# interface.net
KiCad netlist of a schematic drawn in EAGLE
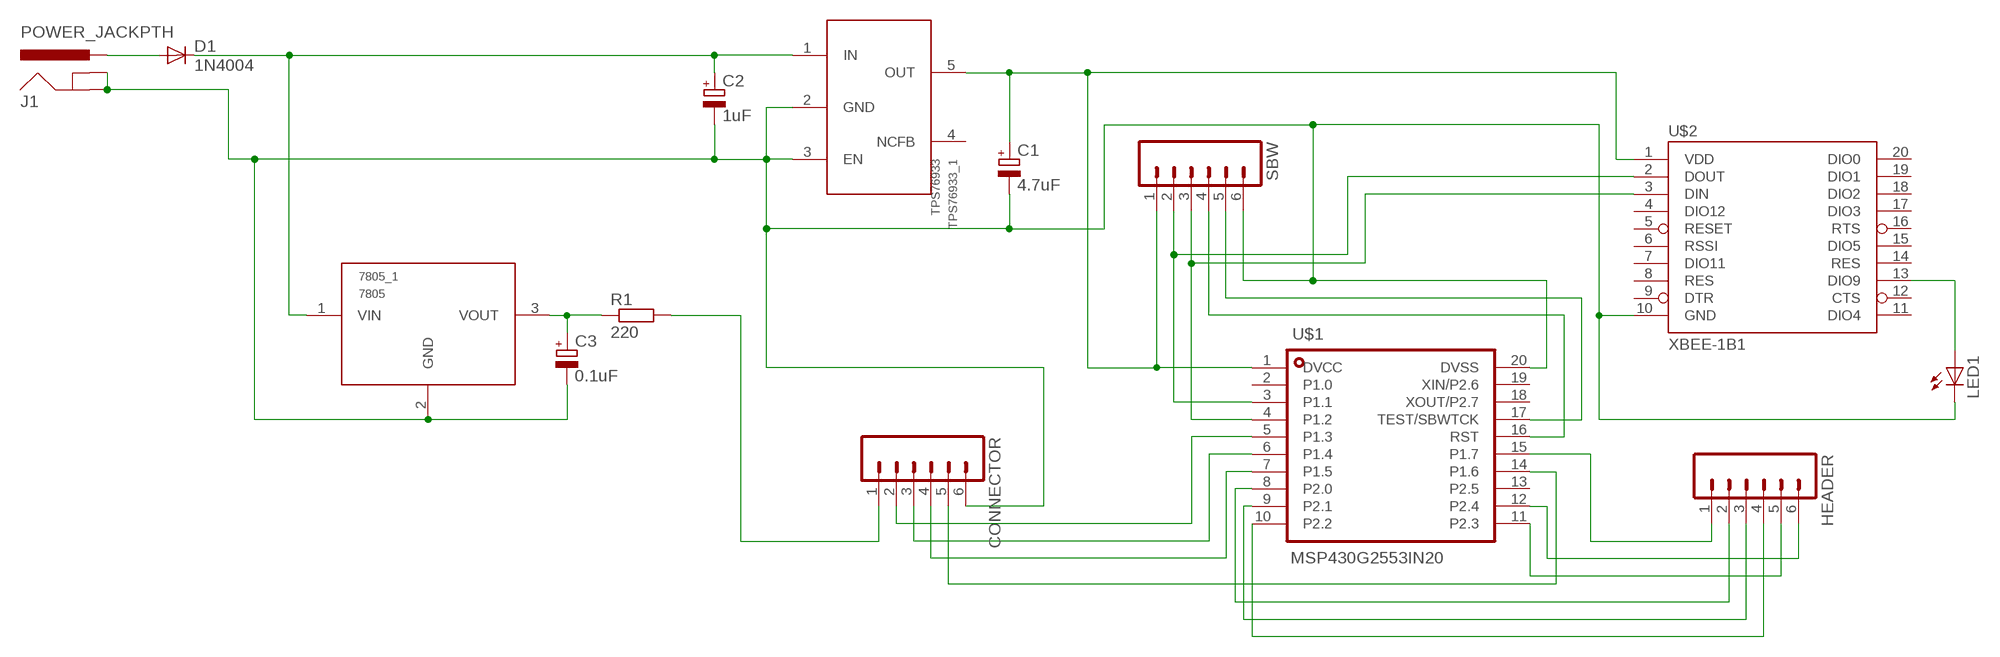
[diagram p0: schematic, sheet 1]

(export (version "E")
  (design (tool "Eeschema 10.0.6"))
  (components
    (comp (ref "7805_1")
      (value "7805")
      (footprint "eagle-import:TO-220")
      (libsource (lib "eagle-import") (part "7805"))
    )
    (comp (ref "C1")
      (value "4.7uF")
      (footprint "eagle-import:E1,8-4")
      (libsource (lib "eagle-import") (part "CPOL-EUE1.8-4"))
    )
    (comp (ref "C2")
      (value "1uF")
      (footprint "eagle-import:E1,8-4")
      (libsource (lib "eagle-import") (part "CPOL-EUE1.8-4"))
    )
    (comp (ref "C3")
      (value "0.1uF")
      (footprint "eagle-import:E1,8-4")
      (libsource (lib "eagle-import") (part "CPOL-EUE1.8-4"))
    )
    (comp (ref "CONNECTOR")
      (value "M06_90SIP")
      (footprint "eagle-import:1X06_90")
      (libsource (lib "eagle-import") (part "M06_90SIP"))
    )
    (comp (ref "D1")
      (value "1N4004")
      (footprint "eagle-import:DO41-10")
      (libsource (lib "eagle-import") (part "1N4004"))
    )
    (comp (ref "HEADER")
      (value "M06_180SIP")
      (footprint "eagle-import:1X06_180")
      (libsource (lib "eagle-import") (part "M06_180SIP"))
    )
    (comp (ref "J1")
      (value "POWER_JACKPTH")
      (footprint "eagle-import:POWER_JACK_PTH")
      (libsource (lib "eagle-import") (part "POWER_JACKPTH"))
    )
    (comp (ref "LED1")
      (value "LED3MM")
      (footprint "eagle-import:LED3MM")
      (libsource (lib "eagle-import") (part "LED3MM"))
    )
    (comp (ref "R1")
      (value "220")
      (footprint "eagle-import:0204_7")
      (libsource (lib "eagle-import") (part "R-EU_0204/7"))
    )
    (comp (ref "SBW")
      (value "M06_180SIP")
      (footprint "eagle-import:1X06_180")
      (libsource (lib "eagle-import") (part "M06_180SIP"))
    )
    (comp (ref "TPS76933_1")
      (value "TPS76933")
      (footprint "eagle-import:SOT23-5")
      (libsource (lib "eagle-import") (part "TPS76933"))
    )
    (comp (ref "U$1")
      (value "MSP430G2553IN20")
      (footprint "eagle-import:DIP20")
      (libsource (lib "eagle-import") (part "MSP430G2553IN20"))
    )
    (comp (ref "U$2")
      (value "XBEE-1B1")
      (footprint "eagle-import:XBEE-1")
      (libsource (lib "eagle-import") (part "XBEE-1B1"))
    )
  )
  (nets
    (net (code "1") (name "Net-(7805_1-GND)") (class "Default")
      (node (ref "7805_1") (pin "2") (pinfunction "GND_2") (pintype "bidirectional"))
      (node (ref "C1") (pin "-") (pinfunction "-_-") (pintype "passive"))
      (node (ref "C2") (pin "-") (pinfunction "-_-") (pintype "passive"))
      (node (ref "C3") (pin "-") (pinfunction "-_-") (pintype "passive"))
      (node (ref "CONNECTOR") (pin "6") (pinfunction "6_6") (pintype "passive"))
      (node (ref "J1") (pin "GND") (pinfunction "GND_GND") (pintype "bidirectional"))
      (node (ref "J1") (pin "GNDBREAK") (pinfunction "GNDBREAK_GNDBREAK") (pintype "bidirectional"))
      (node (ref "LED1") (pin "K") (pinfunction "C_K") (pintype "passive"))
      (node (ref "SBW") (pin "6") (pinfunction "6_6") (pintype "passive"))
      (node (ref "TPS76933_1") (pin "2") (pinfunction "GND_2") (pintype "bidirectional"))
      (node (ref "TPS76933_1") (pin "3") (pinfunction "EN_3") (pintype "bidirectional"))
      (node (ref "U$1") (pin "20") (pinfunction "DVSS_20") (pintype "power_in"))
      (node (ref "U$2") (pin "10") (pinfunction "GND_10") (pintype "power_in"))
    )
    (net (code "2") (name "Net-(7805_1-VIN)") (class "Default")
      (node (ref "7805_1") (pin "1") (pinfunction "VIN_1") (pintype "bidirectional"))
      (node (ref "C2") (pin "+") (pinfunction "+_+") (pintype "passive"))
      (node (ref "D1") (pin "C") (pinfunction "C_C") (pintype "passive"))
      (node (ref "TPS76933_1") (pin "1") (pinfunction "IN_1") (pintype "bidirectional"))
    )
    (net (code "3") (name "Net-(7805_1-VOUT)") (class "Default")
      (node (ref "7805_1") (pin "3") (pinfunction "VOUT_3") (pintype "bidirectional"))
      (node (ref "C3") (pin "+") (pinfunction "+_+") (pintype "passive"))
      (node (ref "R1") (pin "1") (pinfunction "1_1") (pintype "passive"))
    )
    (net (code "4") (name "Net-(CONNECTOR-Pad1)") (class "Default")
      (node (ref "CONNECTOR") (pin "1") (pinfunction "1_1") (pintype "passive"))
      (node (ref "R1") (pin "2") (pinfunction "2_2") (pintype "passive"))
    )
    (net (code "5") (name "Net-(D1-PadA)") (class "Default")
      (node (ref "D1") (pin "A") (pinfunction "A_A") (pintype "passive"))
      (node (ref "J1") (pin "PWR") (pinfunction "PWR_PWR") (pintype "bidirectional"))
    )
    (net (code "6") (name "Net-(TPS76933_1-OUT)") (class "Default")
      (node (ref "C1") (pin "+") (pinfunction "+_+") (pintype "passive"))
      (node (ref "SBW") (pin "1") (pinfunction "1_1") (pintype "passive"))
      (node (ref "TPS76933_1") (pin "5") (pinfunction "OUT_5") (pintype "bidirectional"))
      (node (ref "U$1") (pin "1") (pinfunction "DVCC_1") (pintype "power_in"))
      (node (ref "U$2") (pin "1") (pinfunction "VDD_1") (pintype "power_in"))
    )
    (net (code "7") (name "Net-(U$1-P1.1)") (class "Default")
      (node (ref "SBW") (pin "2") (pinfunction "2_2") (pintype "passive"))
      (node (ref "U$1") (pin "3") (pinfunction "P1.1_3") (pintype "bidirectional"))
      (node (ref "U$2") (pin "2") (pinfunction "DOUT_2") (pintype "output"))
    )
    (net (code "8") (name "Net-(U$1-P1.2)") (class "Default")
      (node (ref "SBW") (pin "3") (pinfunction "3_3") (pintype "passive"))
      (node (ref "U$1") (pin "4") (pinfunction "P1.2_4") (pintype "bidirectional"))
      (node (ref "U$2") (pin "3") (pinfunction "DIN_3") (pintype "input"))
    )
    (net (code "9") (name "Net-(U$1-P1.3)") (class "Default")
      (node (ref "CONNECTOR") (pin "2") (pinfunction "2_2") (pintype "passive"))
      (node (ref "U$1") (pin "5") (pinfunction "P1.3_5") (pintype "bidirectional"))
    )
    (net (code "10") (name "Net-(U$1-P1.4)") (class "Default")
      (node (ref "CONNECTOR") (pin "3") (pinfunction "3_3") (pintype "passive"))
      (node (ref "U$1") (pin "6") (pinfunction "P1.4_6") (pintype "bidirectional"))
    )
    (net (code "11") (name "Net-(U$1-P1.5)") (class "Default")
      (node (ref "CONNECTOR") (pin "4") (pinfunction "4_4") (pintype "passive"))
      (node (ref "U$1") (pin "7") (pinfunction "P1.5_7") (pintype "bidirectional"))
    )
    (net (code "12") (name "Net-(U$1-P1.6)") (class "Default")
      (node (ref "CONNECTOR") (pin "5") (pinfunction "5_5") (pintype "passive"))
      (node (ref "U$1") (pin "14") (pinfunction "P1.6_14") (pintype "bidirectional"))
    )
    (net (code "13") (name "Net-(U$1-P1.7)") (class "Default")
      (node (ref "HEADER") (pin "1") (pinfunction "1_1") (pintype "passive"))
      (node (ref "U$1") (pin "15") (pinfunction "P1.7_15") (pintype "bidirectional"))
    )
    (net (code "14") (name "Net-(U$1-P2.0)") (class "Default")
      (node (ref "HEADER") (pin "2") (pinfunction "2_2") (pintype "passive"))
      (node (ref "U$1") (pin "8") (pinfunction "P2.0_8") (pintype "bidirectional"))
    )
    (net (code "15") (name "Net-(U$1-P2.1)") (class "Default")
      (node (ref "HEADER") (pin "3") (pinfunction "3_3") (pintype "passive"))
      (node (ref "U$1") (pin "9") (pinfunction "P2.1_9") (pintype "bidirectional"))
    )
    (net (code "16") (name "Net-(U$1-P2.2)") (class "Default")
      (node (ref "HEADER") (pin "4") (pinfunction "4_4") (pintype "passive"))
      (node (ref "U$1") (pin "10") (pinfunction "P2.2_10") (pintype "bidirectional"))
    )
    (net (code "17") (name "Net-(U$1-P2.3)") (class "Default")
      (node (ref "HEADER") (pin "5") (pinfunction "5_5") (pintype "passive"))
      (node (ref "U$1") (pin "11") (pinfunction "P2.3_11") (pintype "bidirectional"))
    )
    (net (code "18") (name "Net-(U$1-P2.4)") (class "Default")
      (node (ref "HEADER") (pin "6") (pinfunction "6_6") (pintype "passive"))
      (node (ref "U$1") (pin "12") (pinfunction "P2.4_12") (pintype "bidirectional"))
    )
    (net (code "19") (name "Net-(U$1-RST)") (class "Default")
      (node (ref "SBW") (pin "4") (pinfunction "4_4") (pintype "passive"))
      (node (ref "U$1") (pin "16") (pinfunction "RST_16") (pintype "bidirectional"))
    )
    (net (code "20") (name "Net-(U$1-TEST{slash}SBWTCK)") (class "Default")
      (node (ref "SBW") (pin "5") (pinfunction "5_5") (pintype "passive"))
      (node (ref "U$1") (pin "17") (pinfunction "TEST/SBWTCK_17") (pintype "bidirectional"))
    )
    (net (code "21") (name "Net-(U$2-DIO9)") (class "Default")
      (node (ref "LED1") (pin "A") (pinfunction "A_A") (pintype "passive"))
      (node (ref "U$2") (pin "13") (pinfunction "DIO9_13") (pintype "bidirectional"))
    )
    (net (code "22") (name "unconnected-(TPS76933_1-NCFB-Pad4)") (class "Default")
      (node (ref "TPS76933_1") (pin "4") (pinfunction "NCFB_4") (pintype "bidirectional"))
    )
    (net (code "23") (name "unconnected-(U$1-P1.0-Pad2)") (class "Default")
      (node (ref "U$1") (pin "2") (pinfunction "P1.0_2") (pintype "bidirectional"))
    )
    (net (code "24") (name "unconnected-(U$1-P2.5-Pad13)") (class "Default")
      (node (ref "U$1") (pin "13") (pinfunction "P2.5_13") (pintype "bidirectional"))
    )
    (net (code "25") (name "unconnected-(U$1-XIN{slash}P2.6-Pad19)") (class "Default")
      (node (ref "U$1") (pin "19") (pinfunction "XIN/P2.6_19") (pintype "bidirectional"))
    )
    (net (code "26") (name "unconnected-(U$1-XOUT{slash}P2.7-Pad18)") (class "Default")
      (node (ref "U$1") (pin "18") (pinfunction "XOUT/P2.7_18") (pintype "bidirectional"))
    )
    (net (code "27") (name "unconnected-(U$2-CTS-Pad12)") (class "Default")
      (node (ref "U$2") (pin "12") (pinfunction "CTS_12") (pintype "output"))
    )
    (net (code "28") (name "unconnected-(U$2-DIO0-Pad20)") (class "Default")
      (node (ref "U$2") (pin "20") (pinfunction "DIO0_20") (pintype "bidirectional"))
    )
    (net (code "29") (name "unconnected-(U$2-DIO1-Pad19)") (class "Default")
      (node (ref "U$2") (pin "19") (pinfunction "DIO1_19") (pintype "bidirectional"))
    )
    (net (code "30") (name "unconnected-(U$2-DIO2-Pad18)") (class "Default")
      (node (ref "U$2") (pin "18") (pinfunction "DIO2_18") (pintype "bidirectional"))
    )
    (net (code "31") (name "unconnected-(U$2-DIO3-Pad17)") (class "Default")
      (node (ref "U$2") (pin "17") (pinfunction "DIO3_17") (pintype "bidirectional"))
    )
    (net (code "32") (name "unconnected-(U$2-DIO4-Pad11)") (class "Default")
      (node (ref "U$2") (pin "11") (pinfunction "DIO4_11") (pintype "bidirectional"))
    )
    (net (code "33") (name "unconnected-(U$2-DIO5-Pad15)") (class "Default")
      (node (ref "U$2") (pin "15") (pinfunction "DIO5_15") (pintype "bidirectional"))
    )
    (net (code "34") (name "unconnected-(U$2-DIO11-Pad7)") (class "Default")
      (node (ref "U$2") (pin "7") (pinfunction "DIO11_7") (pintype "bidirectional"))
    )
    (net (code "35") (name "unconnected-(U$2-DIO12-Pad4)") (class "Default")
      (node (ref "U$2") (pin "4") (pinfunction "DIO12_4") (pintype "bidirectional"))
    )
    (net (code "36") (name "unconnected-(U$2-DTR-Pad9)") (class "Default")
      (node (ref "U$2") (pin "9") (pinfunction "DTR_9") (pintype "bidirectional"))
    )
    (net (code "37") (name "unconnected-(U$2-RES-Pad8)") (class "Default")
      (node (ref "U$2") (pin "8") (pinfunction "RES_8") (pintype "bidirectional"))
    )
    (net (code "38") (name "unconnected-(U$2-RES-Pad14)") (class "Default")
      (node (ref "U$2") (pin "14") (pinfunction "RES_14") (pintype "bidirectional"))
    )
    (net (code "39") (name "unconnected-(U$2-RESET-Pad5)") (class "Default")
      (node (ref "U$2") (pin "5") (pinfunction "RESET_5") (pintype "input"))
    )
    (net (code "40") (name "unconnected-(U$2-RSSI-Pad6)") (class "Default")
      (node (ref "U$2") (pin "6") (pinfunction "RSSI_6") (pintype "bidirectional"))
    )
    (net (code "41") (name "unconnected-(U$2-RTS-Pad16)") (class "Default")
      (node (ref "U$2") (pin "16") (pinfunction "RTS_16") (pintype "input"))
    )
  )
)
